# rear.net
KiCad netlist of a schematic drawn in EAGLE
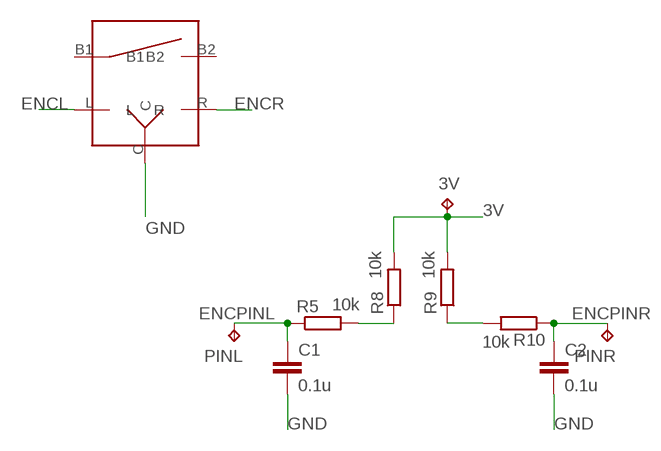
[diagram p0: schematic, sheet 1]

(export (version "E")
  (design (tool "Eeschema 10.0.6"))
  (components
    (comp (ref "3V")
      (value "TPTP14R")
      (footprint "eagle-import:TP14R")
      (libsource (lib "eagle-import") (part "TPTP14R"))
    )
    (comp (ref "C1")
      (value "0.1u")
      (footprint "eagle-import:C0805")
      (libsource (lib "eagle-import") (part "C-EUC0805"))
    )
    (comp (ref "C2")
      (value "0.1u")
      (footprint "eagle-import:C0805")
      (libsource (lib "eagle-import") (part "C-EUC0805"))
    )
    (comp (ref "PINL")
      (value "TPTP14R")
      (footprint "eagle-import:TP14R")
      (libsource (lib "eagle-import") (part "TPTP14R"))
    )
    (comp (ref "PINR")
      (value "TPTP14R")
      (footprint "eagle-import:TP14R")
      (libsource (lib "eagle-import") (part "TPTP14R"))
    )
    (comp (ref "R5")
      (value "10k")
      (footprint "eagle-import:M0805")
      (libsource (lib "eagle-import") (part "R-EU_M0805"))
    )
    (comp (ref "R8")
      (value "10k")
      (footprint "eagle-import:M0805")
      (libsource (lib "eagle-import") (part "R-EU_M0805"))
    )
    (comp (ref "R9")
      (value "10k")
      (footprint "eagle-import:M0805")
      (libsource (lib "eagle-import") (part "R-EU_M0805"))
    )
    (comp (ref "R10")
      (value "10k")
      (footprint "eagle-import:M0805")
      (libsource (lib "eagle-import") (part "R-EU_M0805"))
    )
    (comp (ref "U$1")
      (value "ENCODER")
      (footprint "eagle-import:ENCODER")
      (libsource (lib "eagle-import") (part "ENCODER"))
    )
  )
  (nets
    (net (code "1") (name "/3V") (class "Default")
      (node (ref "3V") (pin "TP") (pinfunction "TP_TP") (pintype "input"))
      (node (ref "R8") (pin "2") (pinfunction "2_2") (pintype "passive"))
      (node (ref "R9") (pin "2") (pinfunction "2_2") (pintype "passive"))
    )
    (net (code "2") (name "/ENCL") (class "Default")
      (node (ref "R5") (pin "2") (pinfunction "2_2") (pintype "passive"))
      (node (ref "R8") (pin "1") (pinfunction "1_1") (pintype "passive"))
      (node (ref "U$1") (pin "L") (pinfunction "L_L") (pintype "bidirectional"))
    )
    (net (code "3") (name "/ENCPINL") (class "Default")
      (node (ref "C1") (pin "1") (pinfunction "1_1") (pintype "passive"))
      (node (ref "PINL") (pin "TP") (pinfunction "TP_TP") (pintype "input"))
      (node (ref "R5") (pin "1") (pinfunction "1_1") (pintype "passive"))
    )
    (net (code "4") (name "/ENCPINR") (class "Default")
      (node (ref "C2") (pin "1") (pinfunction "1_1") (pintype "passive"))
      (node (ref "PINR") (pin "TP") (pinfunction "TP_TP") (pintype "input"))
      (node (ref "R10") (pin "1") (pinfunction "1_1") (pintype "passive"))
    )
    (net (code "5") (name "/ENCR") (class "Default")
      (node (ref "R10") (pin "2") (pinfunction "2_2") (pintype "passive"))
      (node (ref "R9") (pin "1") (pinfunction "1_1") (pintype "passive"))
      (node (ref "U$1") (pin "R") (pinfunction "R_R") (pintype "bidirectional"))
    )
    (net (code "6") (name "/GND") (class "Default")
      (node (ref "C1") (pin "2") (pinfunction "2_2") (pintype "passive"))
      (node (ref "C2") (pin "2") (pinfunction "2_2") (pintype "passive"))
      (node (ref "U$1") (pin "C") (pinfunction "C_C") (pintype "bidirectional"))
    )
    (net (code "7") (name "unconnected-(U$1-PadB1)") (class "Default")
      (node (ref "U$1") (pin "B1") (pinfunction "B1_B1") (pintype "bidirectional"))
    )
    (net (code "8") (name "unconnected-(U$1-PadB2)") (class "Default")
      (node (ref "U$1") (pin "B2") (pinfunction "B2_B2") (pintype "bidirectional"))
    )
  )
)
